# power-supply-board.net
KiCad netlist of a schematic drawn in EAGLE
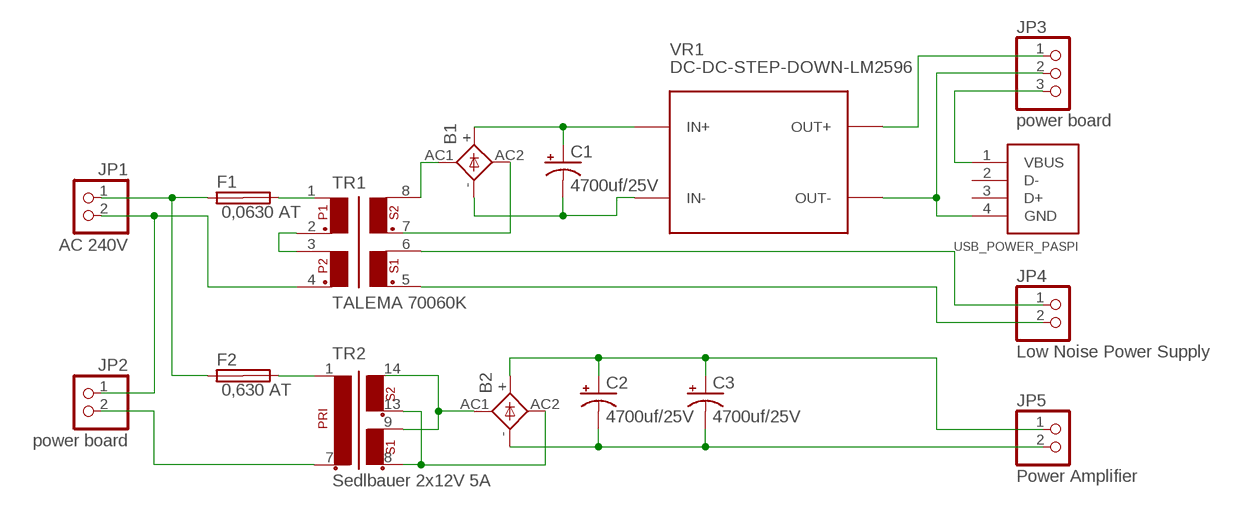
[diagram p0: schematic, sheet 1]

(export (version "E")
  (design (tool "Eeschema 10.0.6"))
  (components
    (comp (ref "B1")
      (value "KBU")
      (footprint "eagle-import:KBU")
      (libsource (lib "eagle-import") (part "KBU"))
    )
    (comp (ref "B2")
      (value "KBU")
      (footprint "eagle-import:KBU")
      (libsource (lib "eagle-import") (part "KBU"))
    )
    (comp (ref "C1")
      (value "4700uf/25V")
      (footprint "eagle-import:CPOL-RADIAL-1000UF-25V-KIT")
      (libsource (lib "eagle-import") (part "1000UF-25V(PTH)KIT"))
    )
    (comp (ref "C2")
      (value "4700uf/25V")
      (footprint "eagle-import:CPOL-RADIAL-1000UF-25V-KIT")
      (libsource (lib "eagle-import") (part "1000UF-25V(PTH)KIT"))
    )
    (comp (ref "C3")
      (value "4700uf/25V")
      (footprint "eagle-import:CPOL-RADIAL-1000UF-25V-KIT")
      (libsource (lib "eagle-import") (part "1000UF-25V(PTH)KIT"))
    )
    (comp (ref "F1")
      (value "0,0630 AT")
      (footprint "eagle-import:SHK20L")
      (libsource (lib "eagle-import") (part "SHK20L"))
    )
    (comp (ref "F2")
      (value "0,630 AT")
      (footprint "eagle-import:SHK20L")
      (libsource (lib "eagle-import") (part "SHK20L"))
    )
    (comp (ref "JP1")
      (value "AC 240V")
      (footprint "eagle-import:1X02")
      (libsource (lib "eagle-import") (part "PINHD-1X2"))
    )
    (comp (ref "JP2")
      (value "power board")
      (footprint "eagle-import:1X02")
      (libsource (lib "eagle-import") (part "PINHD-1X2"))
    )
    (comp (ref "JP3")
      (value "power board")
      (footprint "eagle-import:1X03")
      (libsource (lib "eagle-import") (part "PINHD-1X3"))
    )
    (comp (ref "JP4")
      (value "Low Noise Power Supply")
      (footprint "eagle-import:1X02")
      (libsource (lib "eagle-import") (part "PINHD-1X2"))
    )
    (comp (ref "JP5")
      (value "Power Amplifier")
      (footprint "eagle-import:1X02")
      (libsource (lib "eagle-import") (part "PINHD-1X2"))
    )
    (comp (ref "TR1")
      (value "TALEMA 70060K")
      (footprint "eagle-import:FL10-30")
      (libsource (lib "eagle-import") (part "FL10"))
    )
    (comp (ref "TR2")
      (value "Sedlbauer 2x12V 5A")
      (footprint "eagle-import:EI54-18,8_16VA")
      (libsource (lib "eagle-import") (part "BV054-5387.0K"))
    )
    (comp (ref "USB_POWER_PASPI")
      (value "USB POWER RASPI")
      (footprint "eagle-import:USB-MALE-A-PCB")
      (libsource (lib "eagle-import") (part "USB-CON-4PIN"))
    )
    (comp (ref "VR1")
      (value "DC-DC-STEP-DOWN-LM2596")
      (footprint "eagle-import:DC-DC-STEP-DOWN-LM2596")
      (libsource (lib "eagle-import") (part "DC-DC-STEP-DOWN-LM2596"))
    )
  )
  (nets
    (net (code "1") (name "Net-(B1-Pad+)") (class "Default")
      (node (ref "B1") (pin "+") (pinfunction "+_+") (pintype "passive"))
      (node (ref "C1") (pin "+") (pinfunction "+_+") (pintype "passive"))
      (node (ref "VR1") (pin "IN+") (pinfunction "IN+_IN+") (pintype "bidirectional"))
    )
    (net (code "2") (name "Net-(B1-Pad-)") (class "Default")
      (node (ref "B1") (pin "-") (pinfunction "-_-") (pintype "passive"))
      (node (ref "C1") (pin "-") (pinfunction "-_-") (pintype "passive"))
      (node (ref "VR1") (pin "IN-") (pinfunction "IN-_IN-") (pintype "bidirectional"))
    )
    (net (code "3") (name "Net-(B1-PadAC1)") (class "Default")
      (node (ref "B1") (pin "AC1") (pinfunction "AC1_AC1") (pintype "passive"))
      (node (ref "TR1") (pin "8") (pinfunction "8_8") (pintype "passive"))
    )
    (net (code "4") (name "Net-(B2-Pad+)") (class "Default")
      (node (ref "B2") (pin "+") (pinfunction "+_+") (pintype "passive"))
      (node (ref "C2") (pin "+") (pinfunction "+_+") (pintype "passive"))
      (node (ref "C3") (pin "+") (pinfunction "+_+") (pintype "passive"))
      (node (ref "JP5") (pin "1") (pinfunction "1_1") (pintype "passive"))
    )
    (net (code "5") (name "Net-(B2-Pad-)") (class "Default")
      (node (ref "B2") (pin "-") (pinfunction "-_-") (pintype "passive"))
      (node (ref "C2") (pin "-") (pinfunction "-_-") (pintype "passive"))
      (node (ref "C3") (pin "-") (pinfunction "-_-") (pintype "passive"))
      (node (ref "JP5") (pin "2") (pinfunction "2_2") (pintype "passive"))
    )
    (net (code "6") (name "Net-(F1-Pad1A)") (class "Default")
      (node (ref "F1") (pin "1A") (pinfunction "1A_1A") (pintype "passive"))
      (node (ref "F2") (pin "1A") (pinfunction "1A_1A") (pintype "passive"))
      (node (ref "JP1") (pin "1") (pinfunction "1_1") (pintype "passive"))
    )
    (net (code "7") (name "Net-(F2-Pad2A)") (class "Default")
      (node (ref "F2") (pin "2A") (pinfunction "2A_2A") (pintype "passive"))
      (node (ref "TR2") (pin "1") (pinfunction "1_1") (pintype "passive"))
    )
    (net (code "8") (name "Net-(JP1-Pad2)") (class "Default")
      (node (ref "JP1") (pin "2") (pinfunction "2_2") (pintype "passive"))
      (node (ref "JP2") (pin "1") (pinfunction "1_1") (pintype "passive"))
      (node (ref "TR1") (pin "4") (pinfunction "4_4") (pintype "passive"))
    )
    (net (code "9") (name "Net-(JP3-Pad1)") (class "Default")
      (node (ref "JP3") (pin "1") (pinfunction "1_1") (pintype "passive"))
      (node (ref "VR1") (pin "OUT+") (pinfunction "OUT+_OUT+") (pintype "bidirectional"))
    )
    (net (code "10") (name "Net-(JP4-Pad1)") (class "Default")
      (node (ref "JP4") (pin "1") (pinfunction "1_1") (pintype "passive"))
      (node (ref "TR1") (pin "6") (pinfunction "6_6") (pintype "passive"))
    )
    (net (code "11") (name "Net-(JP4-Pad2)") (class "Default")
      (node (ref "JP4") (pin "2") (pinfunction "2_2") (pintype "passive"))
      (node (ref "TR1") (pin "5") (pinfunction "5_5") (pintype "passive"))
    )
    (net (code "12") (name "Net-(TR1-Pad2)") (class "Default")
      (node (ref "TR1") (pin "2") (pinfunction "2_2") (pintype "passive"))
      (node (ref "TR1") (pin "3") (pinfunction "3_3") (pintype "passive"))
    )
    (net (code "13") (name "Net-(TR2-2)") (class "Default")
      (node (ref "JP2") (pin "2") (pinfunction "2_2") (pintype "passive"))
      (node (ref "TR2") (pin "7") (pinfunction "2_7") (pintype "passive"))
    )
    (net (code "14") (name "Net-(TR2-3)") (class "Default")
      (node (ref "B2") (pin "AC2") (pinfunction "AC2_AC2") (pintype "passive"))
      (node (ref "TR2") (pin "13") (pinfunction "5_13") (pintype "passive"))
      (node (ref "TR2") (pin "8") (pinfunction "3_8") (pintype "passive"))
    )
    (net (code "15") (name "Net-(TR2-4)") (class "Default")
      (node (ref "B2") (pin "AC1") (pinfunction "AC1_AC1") (pintype "passive"))
      (node (ref "TR2") (pin "9") (pinfunction "4_9") (pintype "passive"))
    )
    (net (code "16") (name "Net-(USB_POWER_PASPI-GND)") (class "Default")
      (node (ref "JP3") (pin "2") (pinfunction "2_2") (pintype "passive"))
      (node (ref "USB_POWER_PASPI") (pin "4") (pinfunction "GND_4") (pintype "power_in"))
      (node (ref "VR1") (pin "OUT-") (pinfunction "OUT-_OUT-") (pintype "bidirectional"))
    )
    (net (code "17") (name "Net-(USB_POWER_PASPI-VBUS)") (class "Default")
      (node (ref "JP3") (pin "3") (pinfunction "3_3") (pintype "passive"))
      (node (ref "USB_POWER_PASPI") (pin "1") (pinfunction "VBUS_1") (pintype "power_in"))
    )
    (net (code "18") (name "unconnected-(B1-PadAC2)") (class "Default")
      (node (ref "B1") (pin "AC2") (pinfunction "AC2_AC2") (pintype "passive"))
    )
    (net (code "19") (name "unconnected-(F1-Pad1B)") (class "Default")
      (node (ref "F1") (pin "1B") (pinfunction "1B_1B") (pintype "passive"))
    )
    (net (code "20") (name "unconnected-(F1-Pad2A)") (class "Default")
      (node (ref "F1") (pin "2A") (pinfunction "2A_2A") (pintype "passive"))
    )
    (net (code "21") (name "unconnected-(F1-Pad2B)") (class "Default")
      (node (ref "F1") (pin "2B") (pinfunction "2B_2B") (pintype "passive"))
    )
    (net (code "22") (name "unconnected-(F2-Pad1B)") (class "Default")
      (node (ref "F2") (pin "1B") (pinfunction "1B_1B") (pintype "passive"))
    )
    (net (code "23") (name "unconnected-(F2-Pad2B)") (class "Default")
      (node (ref "F2") (pin "2B") (pinfunction "2B_2B") (pintype "passive"))
    )
    (net (code "24") (name "unconnected-(TR1-Pad1)") (class "Default")
      (node (ref "TR1") (pin "1") (pinfunction "1_1") (pintype "passive"))
    )
    (net (code "25") (name "unconnected-(TR1-Pad7)") (class "Default")
      (node (ref "TR1") (pin "7") (pinfunction "7_7") (pintype "passive"))
    )
    (net (code "26") (name "unconnected-(TR2-6-Pad14)") (class "Default")
      (node (ref "TR2") (pin "14") (pinfunction "6_14") (pintype "passive"))
    )
    (net (code "27") (name "unconnected-(USB_POWER_PASPI-D+-Pad3)") (class "Default")
      (node (ref "USB_POWER_PASPI") (pin "3") (pinfunction "D+_3") (pintype "bidirectional"))
    )
    (net (code "28") (name "unconnected-(USB_POWER_PASPI-D--Pad2)") (class "Default")
      (node (ref "USB_POWER_PASPI") (pin "2") (pinfunction "D-_2") (pintype "bidirectional"))
    )
  )
)
